# ADE9153A_scamatic.net
KiCad netlist of a schematic drawn in EAGLE
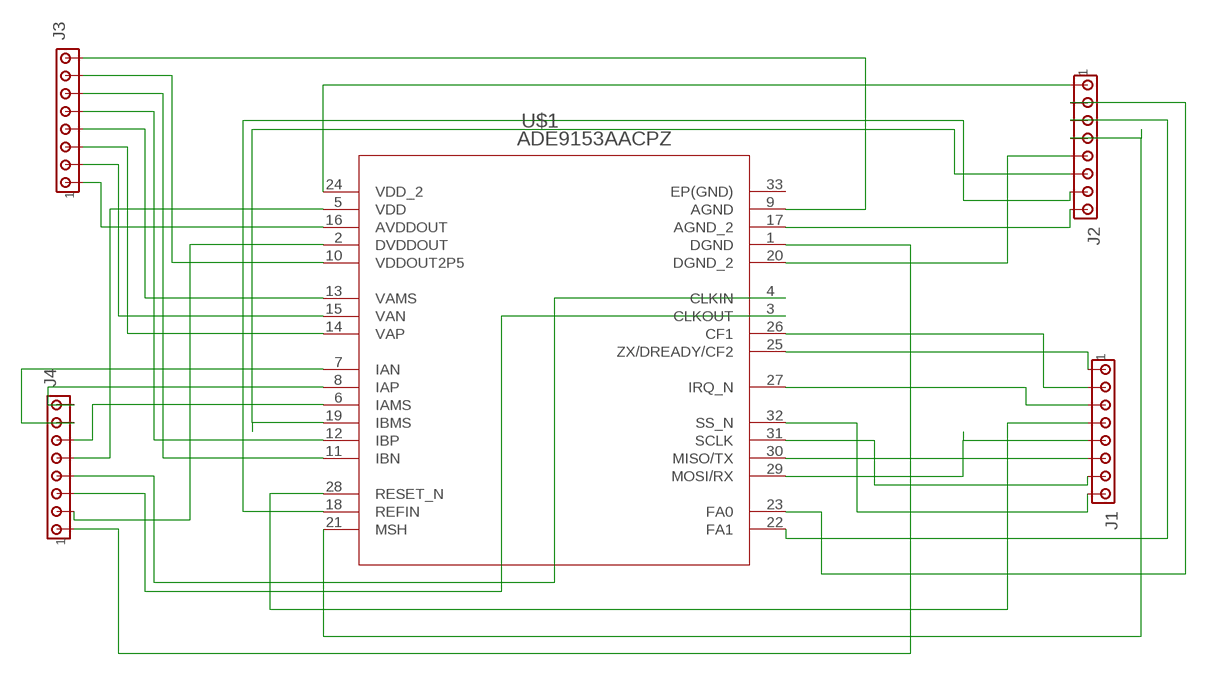
[diagram p0: schematic, sheet 1]

(export (version "E")
  (design (tool "Eeschema 10.0.6"))
  (components
    (comp (ref "J1")
      (value "MTA08-100")
      (footprint "eagle-import:10X08MTA")
      (libsource (lib "eagle-import") (part "MTA08-100"))
    )
    (comp (ref "J2")
      (value "MTA08-100")
      (footprint "eagle-import:10X08MTA")
      (libsource (lib "eagle-import") (part "MTA08-100"))
    )
    (comp (ref "J3")
      (value "MTA08-100")
      (footprint "eagle-import:10X08MTA")
      (libsource (lib "eagle-import") (part "MTA08-100"))
    )
    (comp (ref "J4")
      (value "MTA08-100")
      (footprint "eagle-import:10X08MTA")
      (libsource (lib "eagle-import") (part "MTA08-100"))
    )
    (comp (ref "U$1")
      (value "ADE9153AACPZ")
      (footprint "eagle-import:QFN50P500X500X80-33N")
      (fields (field (name "MF") "Analog Devices"))
      (libsource (lib "eagle-import") (part "ADE9153AACPZ"))
    )
  )
  (nets
    (net (code "1") (name "Net-(U$1-AGND)") (class "Default")
      (node (ref "J3") (pin "8") (pinfunction "8_8") (pintype "passive"))
      (node (ref "U$1") (pin "9") (pinfunction "AGND_9") (pintype "passive"))
    )
    (net (code "2") (name "Net-(U$1-AGND_2)") (class "Default")
      (node (ref "J2") (pin "8") (pinfunction "8_8") (pintype "passive"))
      (node (ref "U$1") (pin "17") (pinfunction "AGND_2_17") (pintype "passive"))
    )
    (net (code "3") (name "Net-(U$1-AVDDOUT)") (class "Default")
      (node (ref "J3") (pin "1") (pinfunction "1_1") (pintype "passive"))
      (node (ref "U$1") (pin "16") (pinfunction "AVDDOUT_16") (pintype "passive"))
    )
    (net (code "4") (name "Net-(U$1-CF1)") (class "Default")
      (node (ref "J1") (pin "2") (pinfunction "2_2") (pintype "passive"))
      (node (ref "U$1") (pin "26") (pinfunction "CF1_26") (pintype "passive"))
    )
    (net (code "5") (name "Net-(U$1-CLKIN)") (class "Default")
      (node (ref "J4") (pin "4") (pinfunction "4_4") (pintype "passive"))
      (node (ref "U$1") (pin "4") (pinfunction "CLKIN_4") (pintype "passive"))
    )
    (net (code "6") (name "Net-(U$1-CLKOUT)") (class "Default")
      (node (ref "J4") (pin "3") (pinfunction "3_3") (pintype "passive"))
      (node (ref "U$1") (pin "3") (pinfunction "CLKOUT_3") (pintype "passive"))
    )
    (net (code "7") (name "Net-(U$1-DGND)") (class "Default")
      (node (ref "J4") (pin "1") (pinfunction "1_1") (pintype "passive"))
      (node (ref "U$1") (pin "1") (pinfunction "DGND_1") (pintype "passive"))
    )
    (net (code "8") (name "Net-(U$1-DGND_2)") (class "Default")
      (node (ref "J2") (pin "5") (pinfunction "5_5") (pintype "passive"))
      (node (ref "U$1") (pin "20") (pinfunction "DGND_2_20") (pintype "passive"))
    )
    (net (code "9") (name "Net-(U$1-DVDDOUT)") (class "Default")
      (node (ref "J4") (pin "2") (pinfunction "2_2") (pintype "passive"))
      (node (ref "U$1") (pin "2") (pinfunction "DVDDOUT_2") (pintype "passive"))
    )
    (net (code "10") (name "Net-(U$1-FA0)") (class "Default")
      (node (ref "J2") (pin "2") (pinfunction "2_2") (pintype "passive"))
      (node (ref "U$1") (pin "23") (pinfunction "FA0_23") (pintype "passive"))
    )
    (net (code "11") (name "Net-(U$1-FA1)") (class "Default")
      (node (ref "J2") (pin "3") (pinfunction "3_3") (pintype "passive"))
      (node (ref "U$1") (pin "22") (pinfunction "FA1_22") (pintype "passive"))
    )
    (net (code "12") (name "Net-(U$1-IAMS)") (class "Default")
      (node (ref "J4") (pin "6") (pinfunction "6_6") (pintype "passive"))
      (node (ref "U$1") (pin "6") (pinfunction "IAMS_6") (pintype "passive"))
    )
    (net (code "13") (name "Net-(U$1-IAN)") (class "Default")
      (node (ref "J4") (pin "7") (pinfunction "7_7") (pintype "passive"))
      (node (ref "U$1") (pin "7") (pinfunction "IAN_7") (pintype "passive"))
    )
    (net (code "14") (name "Net-(U$1-IAP)") (class "Default")
      (node (ref "J4") (pin "8") (pinfunction "8_8") (pintype "passive"))
      (node (ref "U$1") (pin "8") (pinfunction "IAP_8") (pintype "passive"))
    )
    (net (code "15") (name "Net-(U$1-IBMS)") (class "Default")
      (node (ref "J2") (pin "6") (pinfunction "6_6") (pintype "passive"))
      (node (ref "U$1") (pin "19") (pinfunction "IBMS_19") (pintype "passive"))
    )
    (net (code "16") (name "Net-(U$1-IBN)") (class "Default")
      (node (ref "J3") (pin "6") (pinfunction "6_6") (pintype "passive"))
      (node (ref "U$1") (pin "11") (pinfunction "IBN_11") (pintype "passive"))
    )
    (net (code "17") (name "Net-(U$1-IBP)") (class "Default")
      (node (ref "J3") (pin "5") (pinfunction "5_5") (pintype "passive"))
      (node (ref "U$1") (pin "12") (pinfunction "IBP_12") (pintype "passive"))
    )
    (net (code "18") (name "Net-(U$1-IRQ_N)") (class "Default")
      (node (ref "J1") (pin "3") (pinfunction "3_3") (pintype "passive"))
      (node (ref "U$1") (pin "27") (pinfunction "IRQ_N_27") (pintype "passive"))
    )
    (net (code "19") (name "Net-(U$1-MISO{slash}TX)") (class "Default")
      (node (ref "J1") (pin "6") (pinfunction "6_6") (pintype "passive"))
      (node (ref "U$1") (pin "30") (pinfunction "MISO/TX_30") (pintype "passive"))
    )
    (net (code "20") (name "Net-(U$1-MOSI{slash}RX)") (class "Default")
      (node (ref "J1") (pin "5") (pinfunction "5_5") (pintype "passive"))
      (node (ref "U$1") (pin "29") (pinfunction "MOSI/RX_29") (pintype "passive"))
    )
    (net (code "21") (name "Net-(U$1-MSH)") (class "Default")
      (node (ref "J2") (pin "4") (pinfunction "4_4") (pintype "passive"))
      (node (ref "U$1") (pin "21") (pinfunction "MSH_21") (pintype "passive"))
    )
    (net (code "22") (name "Net-(U$1-REFIN)") (class "Default")
      (node (ref "J2") (pin "7") (pinfunction "7_7") (pintype "passive"))
      (node (ref "U$1") (pin "18") (pinfunction "REFIN_18") (pintype "passive"))
    )
    (net (code "23") (name "Net-(U$1-RESET_N)") (class "Default")
      (node (ref "J1") (pin "4") (pinfunction "4_4") (pintype "passive"))
      (node (ref "U$1") (pin "28") (pinfunction "RESET_N_28") (pintype "passive"))
    )
    (net (code "24") (name "Net-(U$1-SCLK)") (class "Default")
      (node (ref "J1") (pin "7") (pinfunction "7_7") (pintype "passive"))
      (node (ref "U$1") (pin "31") (pinfunction "SCLK_31") (pintype "passive"))
    )
    (net (code "25") (name "Net-(U$1-SS_N)") (class "Default")
      (node (ref "J1") (pin "8") (pinfunction "8_8") (pintype "passive"))
      (node (ref "U$1") (pin "32") (pinfunction "SS_N_32") (pintype "passive"))
    )
    (net (code "26") (name "Net-(U$1-VAMS)") (class "Default")
      (node (ref "J3") (pin "4") (pinfunction "4_4") (pintype "passive"))
      (node (ref "U$1") (pin "13") (pinfunction "VAMS_13") (pintype "passive"))
    )
    (net (code "27") (name "Net-(U$1-VAN)") (class "Default")
      (node (ref "J3") (pin "2") (pinfunction "2_2") (pintype "passive"))
      (node (ref "U$1") (pin "15") (pinfunction "VAN_15") (pintype "passive"))
    )
    (net (code "28") (name "Net-(U$1-VAP)") (class "Default")
      (node (ref "J3") (pin "3") (pinfunction "3_3") (pintype "passive"))
      (node (ref "U$1") (pin "14") (pinfunction "VAP_14") (pintype "passive"))
    )
    (net (code "29") (name "Net-(U$1-VDD)") (class "Default")
      (node (ref "J4") (pin "5") (pinfunction "5_5") (pintype "passive"))
      (node (ref "U$1") (pin "5") (pinfunction "VDD_5") (pintype "passive"))
    )
    (net (code "30") (name "Net-(U$1-VDDOUT2P5)") (class "Default")
      (node (ref "J3") (pin "7") (pinfunction "7_7") (pintype "passive"))
      (node (ref "U$1") (pin "10") (pinfunction "VDDOUT2P5_10") (pintype "passive"))
    )
    (net (code "31") (name "Net-(U$1-VDD_2)") (class "Default")
      (node (ref "J2") (pin "1") (pinfunction "1_1") (pintype "passive"))
      (node (ref "U$1") (pin "24") (pinfunction "VDD_2_24") (pintype "passive"))
    )
    (net (code "32") (name "Net-(U$1-ZX{slash}DREADY{slash}CF2)") (class "Default")
      (node (ref "J1") (pin "1") (pinfunction "1_1") (pintype "passive"))
      (node (ref "U$1") (pin "25") (pinfunction "ZX/DREADY/CF2_25") (pintype "passive"))
    )
    (net (code "33") (name "unconnected-(U$1-EP(GND)-Pad33)") (class "Default")
      (node (ref "U$1") (pin "33") (pinfunction "EP(GND)_33") (pintype "passive"))
    )
  )
)
